# Debugger.net
KiCad netlist of a schematic drawn in Altium Designer
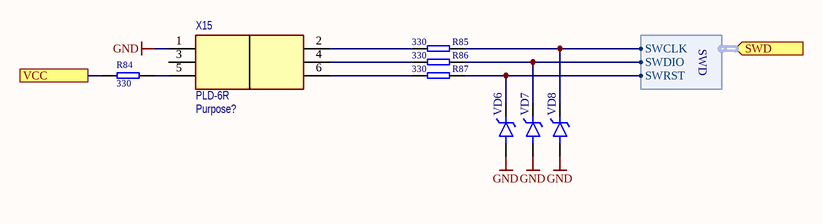
[diagram p0: Debugger.SchDoc]

(export (version "E")
  (design (tool "Eeschema 10.0.6"))
  (components
    (comp (ref "R84")
      (value "330")
      (footprint "RES 0402")
      (description "Resistor")
      (fields (field (name "Comment") "RES 0402 330"))
      (libsource (lib "!main") (part "!Resistor"))
    )
    (comp (ref "R85")
      (value "330")
      (footprint "RES 0402")
      (description "Resistor")
      (fields (field (name "Comment") "RES 0402 330"))
      (libsource (lib "!main") (part "!Resistor"))
    )
    (comp (ref "R86")
      (value "330")
      (footprint "RES 0402")
      (description "Resistor")
      (fields (field (name "Comment") "RES 0402 330"))
      (libsource (lib "!main") (part "!Resistor"))
    )
    (comp (ref "R87")
      (value "330")
      (footprint "RES 0402")
      (description "Resistor")
      (fields (field (name "Comment") "RES 0402 330"))
      (libsource (lib "!main") (part "!Resistor"))
    )
    (comp (ref "VD6")
      (value "DiodeTVSs")
      (footprint "SOD-323")
      (description "Diode TVS Single")
      (libsource (lib "diodes") (part "DiodeTVSs"))
    )
    (comp (ref "VD7")
      (value "DiodeTVSs")
      (footprint "SOD-323")
      (description "Diode TVS Single")
      (libsource (lib "diodes") (part "DiodeTVSs"))
    )
    (comp (ref "VD8")
      (value "DiodeTVSs")
      (footprint "SOD-323")
      (description "Diode TVS Single")
      (libsource (lib "diodes") (part "DiodeTVSs"))
    )
    (comp (ref "X15")
      (value "PLD-6R")
      (footprint "PBD-6-2.54")
      (description "3x2 header")
      (fields (field (name "PURPOSE") "Purpose?"))
      (libsource (lib "connectors") (part "Header 2x3"))
    )
  )
  (nets
    (net (code "2") (name "/VCC") (class "Default")
      (node (ref "R84") (pin "2") (pinfunction "12_2") (pintype "passive"))
    )
    (net (code "4") (name "GND") (class "Default")
      (node (ref "VD6") (pin "A") (pinfunction "Anode_A") (pintype "passive"))
      (node (ref "VD7") (pin "A") (pinfunction "Anode_A") (pintype "passive"))
      (node (ref "VD8") (pin "A") (pinfunction "Anode_A") (pintype "passive"))
      (node (ref "X15") (pin "1") (pinfunction "0_1") (pintype "passive"))
    )
    (net (code "5") (name "Net-(R84-11)") (class "Default")
      (node (ref "R84") (pin "1") (pinfunction "11_1") (pintype "passive"))
      (node (ref "X15") (pin "5") (pinfunction "5_5") (pintype "passive"))
    )
    (net (code "6") (name "Net-(R85-11)") (class "Default")
      (node (ref "R85") (pin "1") (pinfunction "11_1") (pintype "passive"))
      (node (ref "X15") (pin "2") (pinfunction "2_2") (pintype "passive"))
    )
    (net (code "7") (name "Net-(R85-12)") (class "Default")
      (node (ref "R85") (pin "2") (pinfunction "12_2") (pintype "passive"))
      (node (ref "VD8") (pin "C") (pinfunction "Cathode_C") (pintype "passive"))
    )
    (net (code "8") (name "Net-(R86-11)") (class "Default")
      (node (ref "R86") (pin "1") (pinfunction "11_1") (pintype "passive"))
      (node (ref "X15") (pin "4") (pinfunction "4_4") (pintype "passive"))
    )
    (net (code "9") (name "Net-(R86-12)") (class "Default")
      (node (ref "R86") (pin "2") (pinfunction "12_2") (pintype "passive"))
      (node (ref "VD7") (pin "C") (pinfunction "Cathode_C") (pintype "passive"))
    )
    (net (code "10") (name "Net-(R87-11)") (class "Default")
      (node (ref "R87") (pin "1") (pinfunction "11_1") (pintype "passive"))
      (node (ref "X15") (pin "6") (pinfunction "6_6") (pintype "passive"))
    )
    (net (code "11") (name "Net-(R87-12)") (class "Default")
      (node (ref "R87") (pin "2") (pinfunction "12_2") (pintype "passive"))
      (node (ref "VD6") (pin "C") (pinfunction "Cathode_C") (pintype "passive"))
    )
    (net (code "12") (name "unconnected-(X15-Pad3)") (class "Default")
      (node (ref "X15") (pin "3") (pinfunction "3_3") (pintype "passive"))
    )
  )
)
